# M-TrackPad.net
KiCad netlist of a schematic drawn in EAGLE
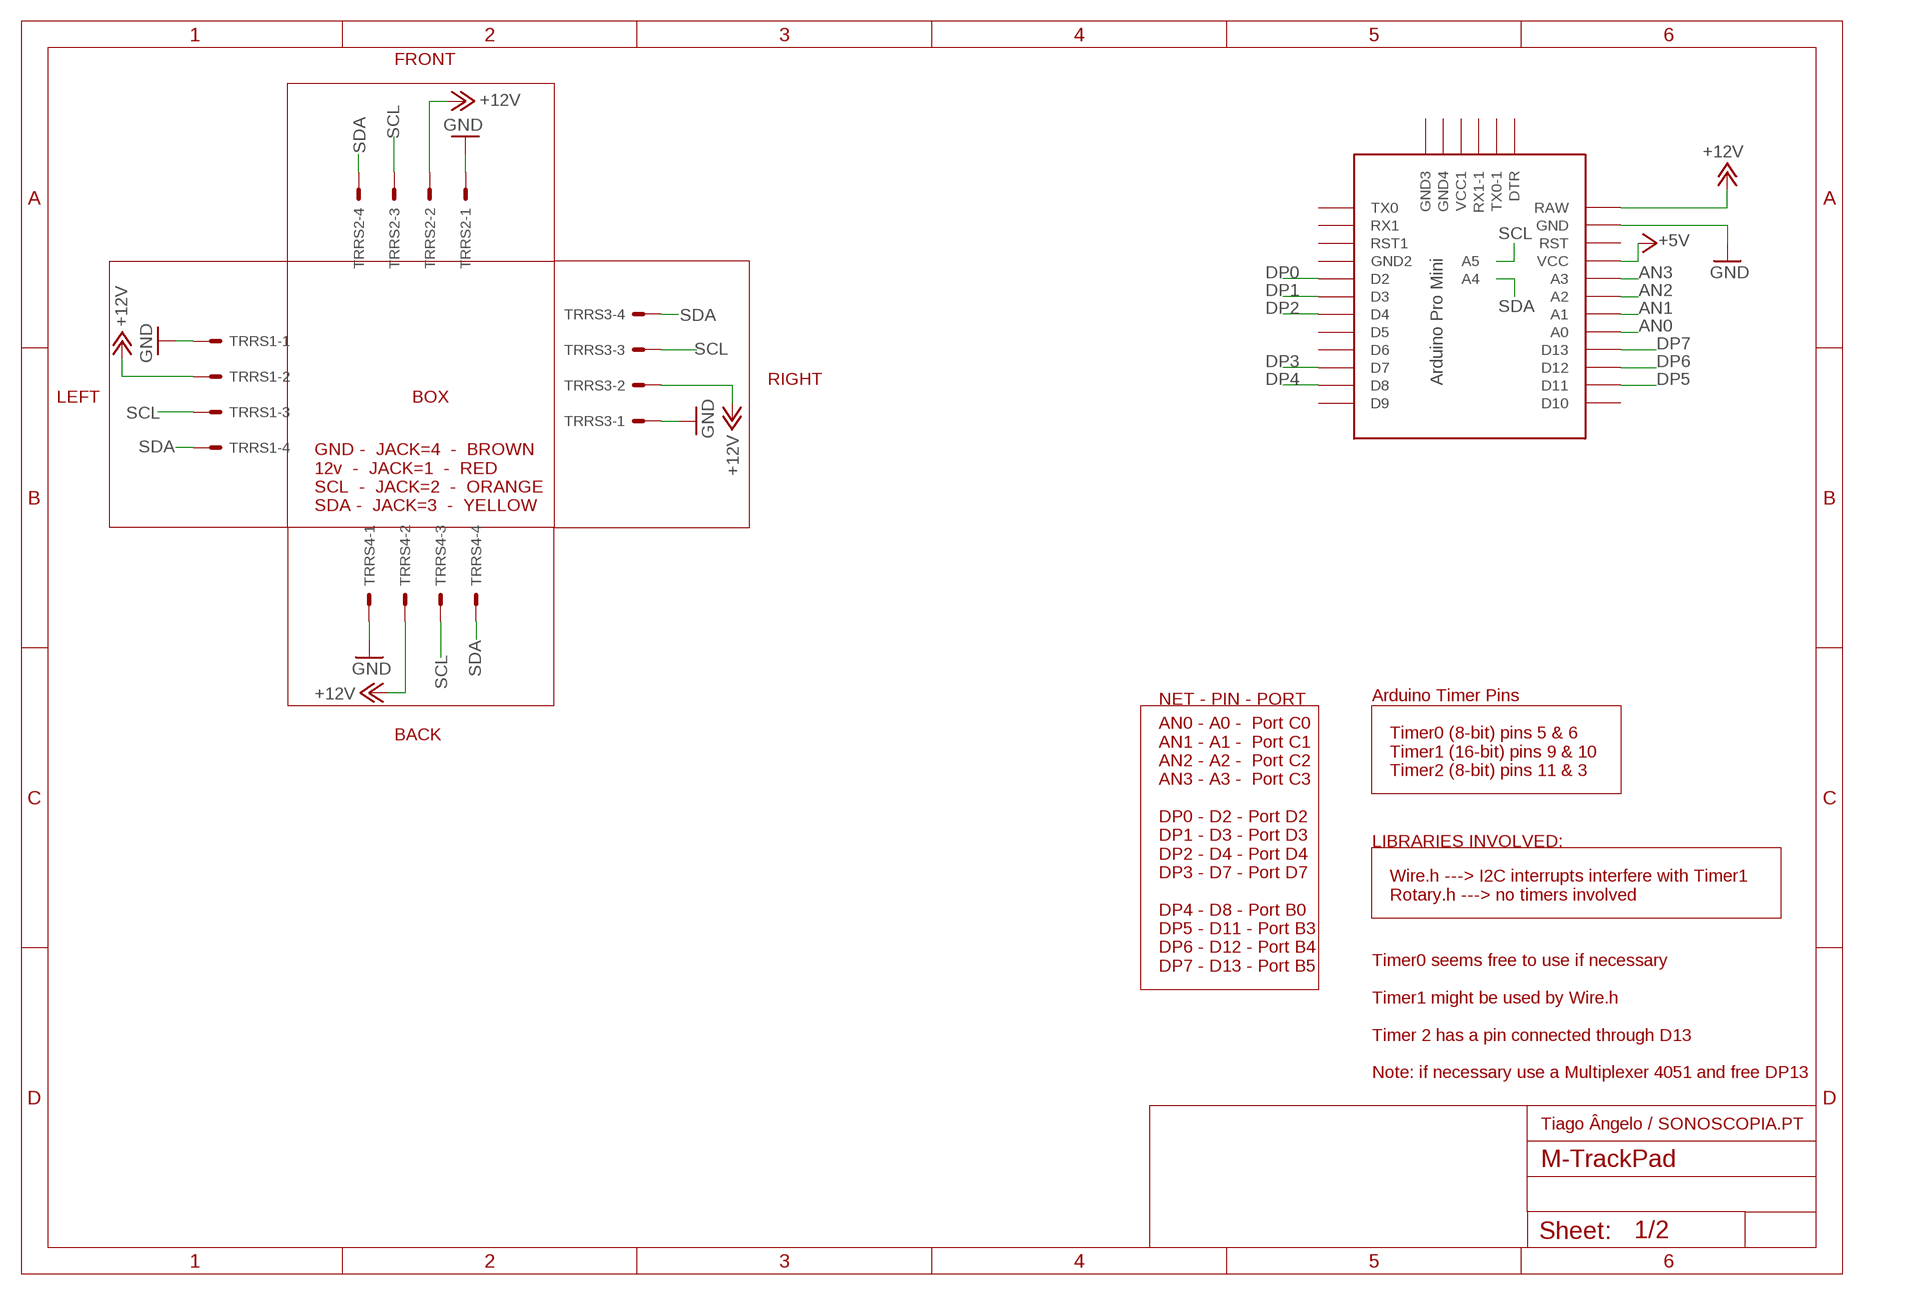
[diagram p0: schematic, sheet 1]
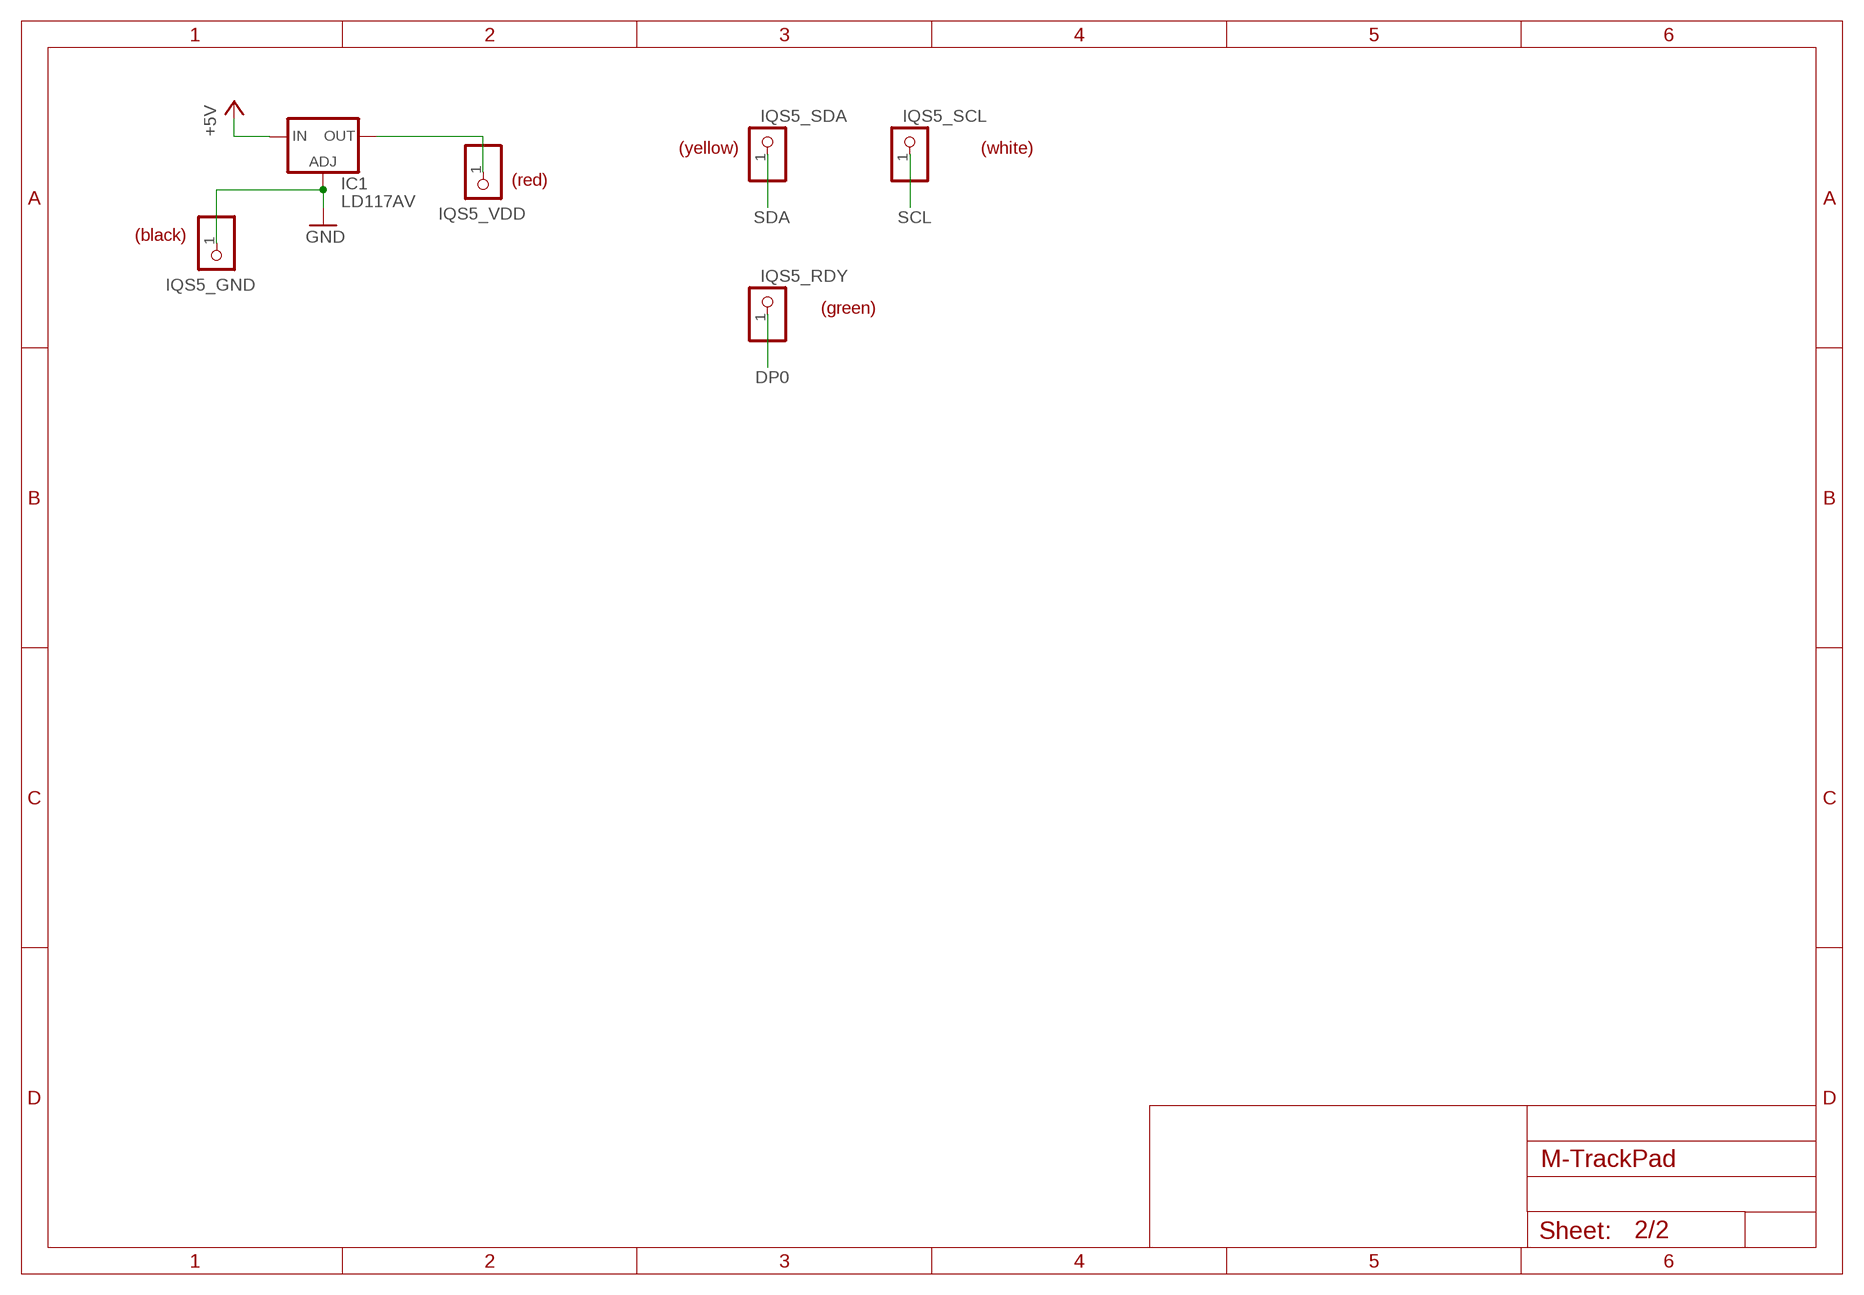
[diagram p1: schematic, sheet 2]

(export (version "E")
  (design (tool "Eeschema 10.0.6"))
  (components
    (comp (ref "TRRS1")
      (value "22-27-2041-04")
      (footprint "eagle-import:6410-04")
      (libsource (lib "eagle-import") (part "22-?-0427-2041"))
    )
    (comp (ref "TRRS2")
      (value "22-27-2041-04")
      (footprint "eagle-import:6410-04")
      (libsource (lib "eagle-import") (part "22-?-0427-2041"))
    )
    (comp (ref "TRRS3")
      (value "22-27-2041-04")
      (footprint "eagle-import:6410-04")
      (libsource (lib "eagle-import") (part "22-?-0427-2041"))
    )
    (comp (ref "TRRS4")
      (value "22-27-2041-04")
      (footprint "eagle-import:6410-04")
      (libsource (lib "eagle-import") (part "22-?-0427-2041"))
    )
    (comp (ref "U$1")
      (value "PRO-MINI-2")
      (footprint "eagle-import:PRO-MINI-2")
      (libsource (lib "eagle-import") (part "PRO-MINI-2"))
    )
    (comp (ref "IC1")
      (value "LD117AV")
      (footprint "eagle-import:TO220L1")
      (libsource (lib "eagle-import") (part "LD117A?V"))
    )
    (comp (ref "IQS5_GND")
      (value "PINHD-1X1")
      (footprint "eagle-import:1X01")
      (libsource (lib "eagle-import") (part "PINHD-1X1"))
    )
    (comp (ref "IQS5_RDY")
      (value "PINHD-1X1")
      (footprint "eagle-import:1X01")
      (libsource (lib "eagle-import") (part "PINHD-1X1"))
    )
    (comp (ref "IQS5_SCL")
      (value "PINHD-1X1")
      (footprint "eagle-import:1X01")
      (libsource (lib "eagle-import") (part "PINHD-1X1"))
    )
    (comp (ref "IQS5_SDA")
      (value "PINHD-1X1")
      (footprint "eagle-import:1X01")
      (libsource (lib "eagle-import") (part "PINHD-1X1"))
    )
    (comp (ref "IQS5_VDD")
      (value "PINHD-1X1")
      (footprint "eagle-import:1X01")
      (libsource (lib "eagle-import") (part "PINHD-1X1"))
    )
  )
  (nets
    (net (code "1") (name "+5V") (class "Default")
      (node (ref "IC1") (pin "3") (pinfunction "IN_3") (pintype "input"))
      (node (ref "U$1") (pin "VCC") (pinfunction "VCC_VCC") (pintype "bidirectional"))
    )
    (net (code "2") (name "+12V") (class "Default")
      (node (ref "TRRS1") (pin "2") (pinfunction "S_2") (pintype "passive"))
      (node (ref "TRRS2") (pin "2") (pinfunction "S_2") (pintype "passive"))
      (node (ref "TRRS3") (pin "2") (pinfunction "S_2") (pintype "passive"))
      (node (ref "TRRS4") (pin "2") (pinfunction "S_2") (pintype "passive"))
      (node (ref "U$1") (pin "RAW") (pinfunction "RAW_RAW") (pintype "bidirectional"))
    )
    (net (code "3") (name "AN0") (class "Default")
      (node (ref "U$1") (pin "A0") (pinfunction "A0_A0") (pintype "bidirectional"))
    )
    (net (code "4") (name "AN1") (class "Default")
      (node (ref "U$1") (pin "A1") (pinfunction "A1_A1") (pintype "bidirectional"))
    )
    (net (code "5") (name "AN2") (class "Default")
      (node (ref "U$1") (pin "A2") (pinfunction "A2_A2") (pintype "bidirectional"))
    )
    (net (code "6") (name "AN3") (class "Default")
      (node (ref "U$1") (pin "A3") (pinfunction "A3_A3") (pintype "bidirectional"))
    )
    (net (code "7") (name "DP0") (class "Default")
      (node (ref "IQS5_RDY") (pin "1") (pinfunction "1_1") (pintype "passive"))
      (node (ref "U$1") (pin "D2") (pinfunction "D2_D2") (pintype "bidirectional"))
    )
    (net (code "8") (name "DP1") (class "Default")
      (node (ref "U$1") (pin "D3") (pinfunction "D3_D3") (pintype "bidirectional"))
    )
    (net (code "9") (name "DP2") (class "Default")
      (node (ref "U$1") (pin "D4") (pinfunction "D4_D4") (pintype "bidirectional"))
    )
    (net (code "10") (name "DP3") (class "Default")
      (node (ref "U$1") (pin "D7") (pinfunction "D7_D7") (pintype "bidirectional"))
    )
    (net (code "11") (name "DP4") (class "Default")
      (node (ref "U$1") (pin "D8") (pinfunction "D8_D8") (pintype "bidirectional"))
    )
    (net (code "12") (name "DP5") (class "Default")
      (node (ref "U$1") (pin "D11") (pinfunction "D11_D11") (pintype "bidirectional"))
    )
    (net (code "13") (name "DP6") (class "Default")
      (node (ref "U$1") (pin "D12") (pinfunction "D12_D12") (pintype "bidirectional"))
    )
    (net (code "14") (name "DP7") (class "Default")
      (node (ref "U$1") (pin "D13") (pinfunction "D13_D13") (pintype "bidirectional"))
    )
    (net (code "15") (name "GND") (class "Default")
      (node (ref "IC1") (pin "1") (pinfunction "ADJ_1") (pintype "input"))
      (node (ref "IQS5_GND") (pin "1") (pinfunction "1_1") (pintype "passive"))
      (node (ref "TRRS1") (pin "1") (pinfunction "S_1") (pintype "passive"))
      (node (ref "TRRS2") (pin "1") (pinfunction "S_1") (pintype "passive"))
      (node (ref "TRRS3") (pin "1") (pinfunction "S_1") (pintype "passive"))
      (node (ref "TRRS4") (pin "1") (pinfunction "S_1") (pintype "passive"))
      (node (ref "U$1") (pin "GND") (pinfunction "GND_GND") (pintype "bidirectional"))
    )
    (net (code "16") (name "Net-(IC1-OUT)") (class "Default")
      (node (ref "IC1") (pin "2") (pinfunction "OUT_2") (pintype "passive"))
      (node (ref "IQS5_VDD") (pin "1") (pinfunction "1_1") (pintype "passive"))
    )
    (net (code "17") (name "SCL") (class "Default")
      (node (ref "IQS5_SCL") (pin "1") (pinfunction "1_1") (pintype "passive"))
      (node (ref "TRRS1") (pin "3") (pinfunction "S_3") (pintype "passive"))
      (node (ref "TRRS2") (pin "3") (pinfunction "S_3") (pintype "passive"))
      (node (ref "TRRS3") (pin "3") (pinfunction "S_3") (pintype "passive"))
      (node (ref "TRRS4") (pin "3") (pinfunction "S_3") (pintype "passive"))
      (node (ref "U$1") (pin "A5") (pinfunction "A5_A5") (pintype "bidirectional"))
    )
    (net (code "18") (name "SDA") (class "Default")
      (node (ref "IQS5_SDA") (pin "1") (pinfunction "1_1") (pintype "passive"))
      (node (ref "TRRS1") (pin "4") (pinfunction "S_4") (pintype "passive"))
      (node (ref "TRRS2") (pin "4") (pinfunction "S_4") (pintype "passive"))
      (node (ref "TRRS3") (pin "4") (pinfunction "S_4") (pintype "passive"))
      (node (ref "TRRS4") (pin "4") (pinfunction "S_4") (pintype "passive"))
      (node (ref "U$1") (pin "A4") (pinfunction "A4_A4") (pintype "bidirectional"))
    )
    (net (code "19") (name "unconnected-(U$1-GND2-PadGND1)") (class "Default")
      (node (ref "U$1") (pin "GND1") (pinfunction "GND2_GND1") (pintype "bidirectional"))
    )
    (net (code "20") (name "unconnected-(U$1-GND3-PadGND2)") (class "Default")
      (node (ref "U$1") (pin "GND2") (pinfunction "GND3_GND2") (pintype "bidirectional"))
    )
    (net (code "21") (name "unconnected-(U$1-GND4-PadGND3)") (class "Default")
      (node (ref "U$1") (pin "GND3") (pinfunction "GND4_GND3") (pintype "bidirectional"))
    )
    (net (code "22") (name "unconnected-(U$1-PadD5)") (class "Default")
      (node (ref "U$1") (pin "D5") (pinfunction "D5_D5") (pintype "bidirectional"))
    )
    (net (code "23") (name "unconnected-(U$1-PadD6)") (class "Default")
      (node (ref "U$1") (pin "D6") (pinfunction "D6_D6") (pintype "bidirectional"))
    )
    (net (code "24") (name "unconnected-(U$1-PadD9)") (class "Default")
      (node (ref "U$1") (pin "D9") (pinfunction "D9_D9") (pintype "bidirectional"))
    )
    (net (code "25") (name "unconnected-(U$1-PadD10)") (class "Default")
      (node (ref "U$1") (pin "D10") (pinfunction "D10_D10") (pintype "bidirectional"))
    )
    (net (code "26") (name "unconnected-(U$1-PadDTR)") (class "Default")
      (node (ref "U$1") (pin "DTR") (pinfunction "DTR_DTR") (pintype "bidirectional"))
    )
    (net (code "27") (name "unconnected-(U$1-PadRST)") (class "Default")
      (node (ref "U$1") (pin "RST") (pinfunction "RST_RST") (pintype "bidirectional"))
    )
    (net (code "28") (name "unconnected-(U$1-PadRST1)") (class "Default")
      (node (ref "U$1") (pin "RST1") (pinfunction "RST1_RST1") (pintype "bidirectional"))
    )
    (net (code "29") (name "unconnected-(U$1-PadRX1)") (class "Default")
      (node (ref "U$1") (pin "RX1") (pinfunction "RX1_RX1") (pintype "bidirectional"))
    )
    (net (code "30") (name "unconnected-(U$1-PadRX1-1)") (class "Default")
      (node (ref "U$1") (pin "RX1-1") (pinfunction "RX1-1_RX1-1") (pintype "bidirectional"))
    )
    (net (code "31") (name "unconnected-(U$1-PadTX0)") (class "Default")
      (node (ref "U$1") (pin "TX0") (pinfunction "TX0_TX0") (pintype "bidirectional"))
    )
    (net (code "32") (name "unconnected-(U$1-PadTX0-1)") (class "Default")
      (node (ref "U$1") (pin "TX0-1") (pinfunction "TX0-1_TX0-1") (pintype "bidirectional"))
    )
    (net (code "33") (name "unconnected-(U$1-PadVCC1)") (class "Default")
      (node (ref "U$1") (pin "VCC1") (pinfunction "VCC1_VCC1") (pintype "bidirectional"))
    )
  )
)
